# 02_MCU.net
KiCad netlist of a schematic drawn in Altium Designer
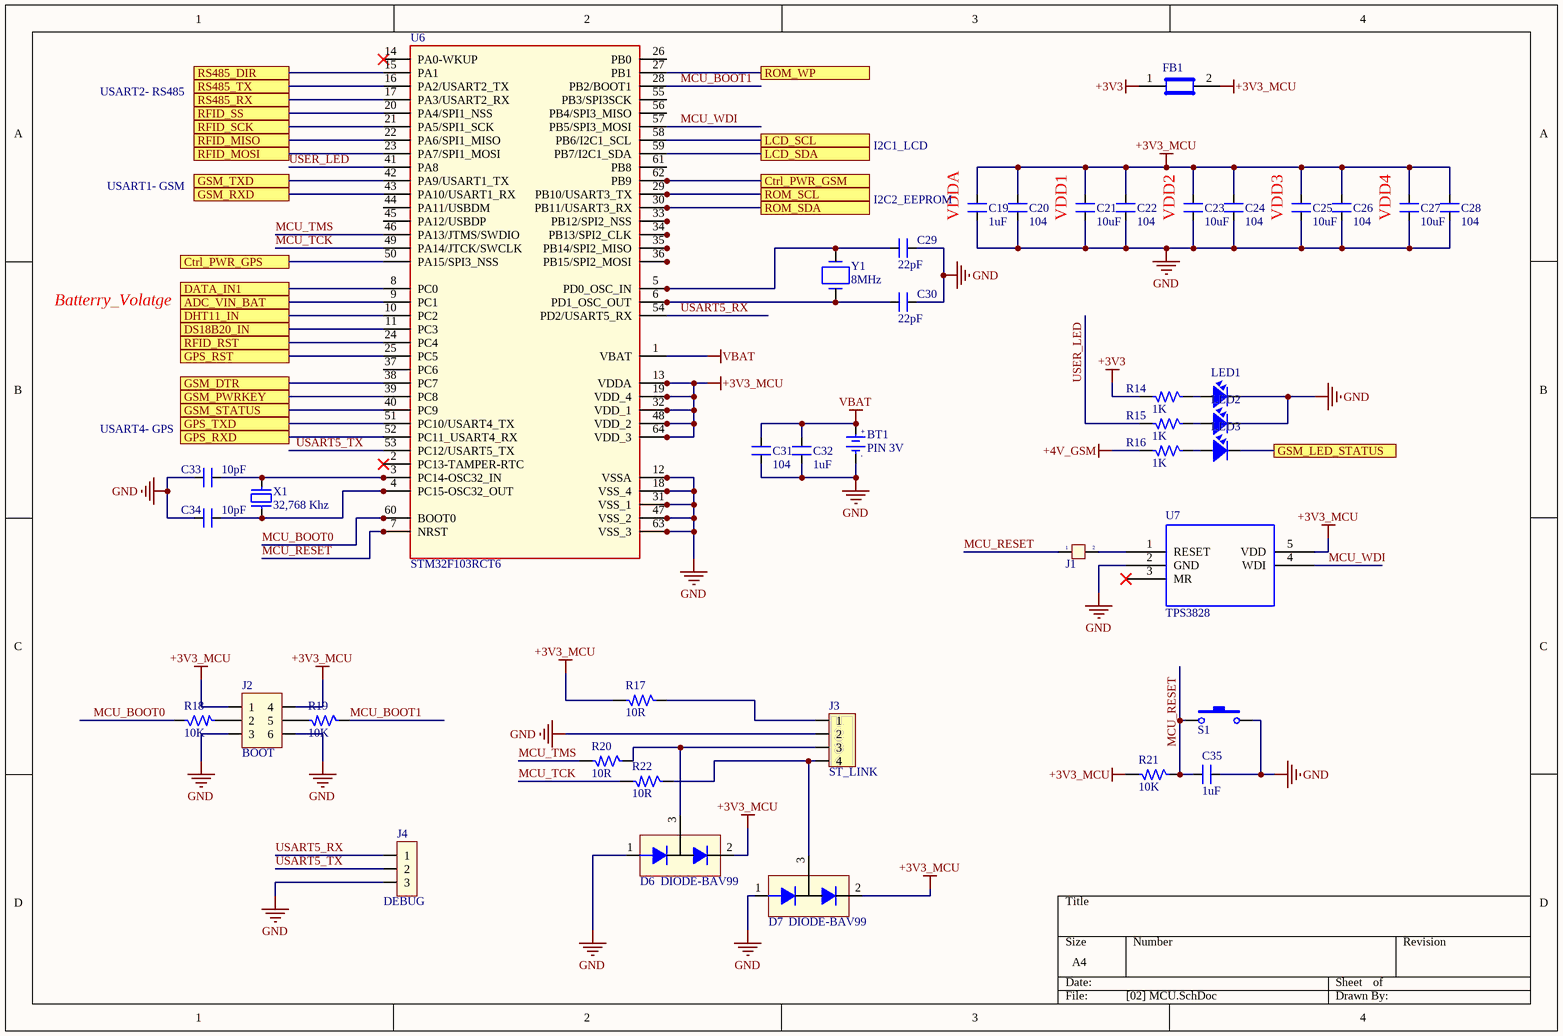
[diagram p0: [02] MCU.SchDoc]

(export (version "E")
  (design (tool "Eeschema 10.0.6"))
  (components
    (comp (ref "BT1")
      (value "PIN 3V")
      (footprint "CR1220 SMD")
      (description "Battery 3VDC")
      (libsource (lib "My Library") (part "PIN 3V"))
    )
    (comp (ref "C19")
      (value "1uF")
      (footprint "C0603 SMT")
      (description "Cap SMD")
      (libsource (lib "GPS_Traking_V1_1") (part "CM"))
    )
    (comp (ref "C20")
      (value "104")
      (footprint "C0603 SMT")
      (description "Cap SMD")
      (libsource (lib "GPS_Traking_V1_1") (part "CM"))
    )
    (comp (ref "C21")
      (value "10uF")
      (footprint "C0603 SMT")
      (description "Cap SMD")
      (libsource (lib "GPS_Traking_V1_1") (part "CM"))
    )
    (comp (ref "C22")
      (value "104")
      (footprint "C0603 SMT")
      (description "Cap SMD")
      (libsource (lib "GPS_Traking_V1_1") (part "CM"))
    )
    (comp (ref "C23")
      (value "10uF")
      (footprint "C0603 SMT")
      (description "Cap SMD")
      (libsource (lib "GPS_Traking_V1_1") (part "CM"))
    )
    (comp (ref "C24")
      (value "104")
      (footprint "C0603 SMT")
      (description "Cap SMD")
      (libsource (lib "GPS_Traking_V1_1") (part "CM"))
    )
    (comp (ref "C25")
      (value "10uF")
      (footprint "C0603 SMT")
      (description "Cap SMD")
      (libsource (lib "GPS_Traking_V1_1") (part "CM"))
    )
    (comp (ref "C26")
      (value "104")
      (footprint "C0603 SMT")
      (description "Cap SMD")
      (libsource (lib "GPS_Traking_V1_1") (part "CM"))
    )
    (comp (ref "C27")
      (value "10uF")
      (footprint "C0603 SMT")
      (description "Cap SMD")
      (libsource (lib "GPS_Traking_V1_1") (part "CM"))
    )
    (comp (ref "C28")
      (value "104")
      (footprint "C0603 SMT")
      (description "Cap SMD")
      (libsource (lib "GPS_Traking_V1_1") (part "CM"))
    )
    (comp (ref "C29")
      (value "22pF")
      (footprint "C0603 SMT")
      (description "Cap SMD")
      (libsource (lib "GPS_Traking_V1_1") (part "CM"))
    )
    (comp (ref "C30")
      (value "22pF")
      (footprint "GPS_Traking_V1_1:C0603 SMT")
      (description "Cap SMD")
      (libsource (lib "My Library") (part "CM"))
    )
    (comp (ref "C31")
      (value "104")
      (footprint "C0603 SMT")
      (description "Cap SMD")
      (libsource (lib "GPS_Traking_V1_1") (part "CM"))
    )
    (comp (ref "C32")
      (value "1uF")
      (footprint "GPS_Traking_V1_1:C0603 SMT")
      (description "Cap SMD")
      (libsource (lib "My Library") (part "CM"))
    )
    (comp (ref "C33")
      (value "10pF")
      (footprint "C0603 SMT")
      (description "Cap SMD")
      (libsource (lib "GPS_Traking_V1_1") (part "CM"))
    )
    (comp (ref "C34")
      (value "10pF")
      (footprint "C0603 SMT")
      (description "Cap SMD")
      (libsource (lib "GPS_Traking_V1_1") (part "CM"))
    )
    (comp (ref "C35")
      (value "1uF")
      (footprint "CAP_0805")
      (description "Cap SMD")
      (libsource (lib "GPS_Traking_V1_1") (part "CM"))
    )
    (comp (ref "D6")
      (value "DIODE-BAV99")
      (footprint "SOT23")
      (description "ZENER, SOT23,")
      (fields
        (field (name "MANUFACTURER") "ON Semiconductor / Fairchild")
        (field (name "MANUFACTURER PART NUMBER") "BAV99")
        (field (name ".CREATOR") "LeKhaLinh")
        (field (name ".CHECKPCB") "LeKhaLinh")
        (field (name ".CHECKSCH") "LeKhaLinh")
      )
      (libsource (lib "GPS_Traking_V1_1") (part "DIODE-BAV99"))
    )
    (comp (ref "D7")
      (value "DIODE-BAV99")
      (footprint "SOT23")
      (description "ZENER, SOT23,")
      (fields
        (field (name "MANUFACTURER") "ON Semiconductor / Fairchild")
        (field (name "MANUFACTURER PART NUMBER") "BAV99")
        (field (name ".CREATOR") "LeKhaLinh")
        (field (name ".CHECKPCB") "LeKhaLinh")
        (field (name ".CHECKSCH") "LeKhaLinh")
      )
      (libsource (lib "GPS_Traking_V1_1") (part "DIODE-BAV99"))
    )
    (comp (ref "FB1")
      (value "BLM21PG600SN1D")
      (footprint "GPS_Traking_V1_1:R0805")
      (description "Ferrite Bead")
      (libsource (lib "khapham") (part "Ferrite Bead"))
    )
    (comp (ref "J1")
      (value "watdog")
      (footprint "JP2")
      (description "Jumper 2")
      (libsource (lib "GPS_Traking_V1_1") (part "JP 2"))
    )
    (comp (ref "J2")
      (value "BOOT")
      (footprint "JP3x2")
      (description "Connector 3x2")
      (libsource (lib "GPS_Traking_V1_1") (part "JP3x2"))
    )
    (comp (ref "J3")
      (value "ST_LINK")
      (footprint "CON_4P")
      (description "Header IDC, 4 x 1 Pin Vertical 2.54mm Pitch (Non-Boxed, Male)")
      (fields
        (field (name "MANUFACTURER") "Würth Elektronik eiSos GmbH")
        (field (name "PARTNO") "613002143121")
        (field (name "CREATED BY") "Karrer Zheng")
      )
      (libsource (lib "My Library") (part "Header4"))
    )
    (comp (ref "J4")
      (value "DEBUG")
      (footprint "JP3")
      (description "Jumper 3")
      (libsource (lib "My Library") (part "JP3"))
    )
    (comp (ref "LED1")
      (value "LED")
      (footprint "LED-0805-Green")
      (description "LED Single colour Green and Red")
      (libsource (lib "My Library") (part "LED"))
    )
    (comp (ref "LED2")
      (value "LED")
      (footprint "LED-0805-Yellow")
      (description "LED Single colour Green and Red")
      (libsource (lib "My Library") (part "LED"))
    )
    (comp (ref "LED3")
      (value "LED")
      (footprint "LED-0805-Red")
      (description "LED Single colour Green and Red")
      (libsource (lib "My Library") (part "LED"))
    )
    (comp (ref "R14")
      (value "1K")
      (footprint "RES-SMD-0805")
      (description "Resistor SMD")
      (libsource (lib "GPS_Traking_V1_1") (part "RM"))
    )
    (comp (ref "R15")
      (value "1K")
      (footprint "RES-SMD-0805")
      (description "Resistor SMD")
      (libsource (lib "GPS_Traking_V1_1") (part "RM"))
    )
    (comp (ref "R16")
      (value "1K")
      (footprint "RES-SMD-0805")
      (description "Resistor SMD")
      (libsource (lib "GPS_Traking_V1_1") (part "RM"))
    )
    (comp (ref "R17")
      (value "10R")
      (footprint "RES-SMD-0805")
      (description "Resistor SMD")
      (libsource (lib "GPS_Traking_V1_1") (part "RM"))
    )
    (comp (ref "R18")
      (value "10K")
      (footprint "R0603 -SMT")
      (description "Resistor SMD")
      (libsource (lib "GPS_Traking_V1_1") (part "RM"))
    )
    (comp (ref "R19")
      (value "10K")
      (footprint "R0603 -SMT")
      (description "Resistor SMD")
      (libsource (lib "GPS_Traking_V1_1") (part "RM"))
    )
    (comp (ref "R20")
      (value "10R")
      (footprint "RES-SMD-0805")
      (description "Resistor SMD")
      (libsource (lib "GPS_Traking_V1_1") (part "RM"))
    )
    (comp (ref "R21")
      (value "10K")
      (footprint "RES-SMD-0805")
      (description "Resistor SMD")
      (libsource (lib "GPS_Traking_V1_1") (part "RM"))
    )
    (comp (ref "R22")
      (value "10R")
      (footprint "RES-SMD-0805")
      (description "Resistor SMD")
      (libsource (lib "GPS_Traking_V1_1") (part "RM"))
    )
    (comp (ref "S1")
      (value "SW-SMD")
      (footprint "SW-SMD")
      (description "Switch")
      (fields (field (name "PUBLISHER") "Altium Limited"))
      (libsource (lib "My Library") (part "SW-SMD"))
    )
    (comp (ref "U6")
      (value "STM32F103RCT6")
      (footprint "LQFP-64")
      (description "MCU 32BIT 256KB FLASH 64LQFP")
      (libsource (lib "GPS_Traking_V1_1") (part "STM32F103RCT6"))
    )
    (comp (ref "U7")
      (value "TPS3828")
      (footprint "TPS3828")
      (libsource (lib "GPS_Traking_V1_1") (part "TPS3828"))
    )
    (comp (ref "X1")
      (value "32,768 Khz")
      (footprint "XT32kn")
      (description "Crystal 32,768kHz for timer real")
      (libsource (lib "GPS_Traking_V1_1") (part "XT32k"))
    )
    (comp (ref "Y1")
      (value "8MHz")
      (footprint "GPS_Traking_V1_1:ABM7_v1_1_BIG")
      (description "CRYSTAL 16MHZ 18PF SMD")
      (fields
        (field (name "MANUFACTURER") "Abracon LLC")
        (field (name "MANUFACTURER PART NUMBER") "ABM7-16.000MHZ-D2Y-T")
        (field (name ".CREATOR") "MM")
        (field (name ".CHECKED PCB") "RF")
        (field (name ".CHECKED SCH") "RF")
      )
      (libsource (lib "GPS_Traking_V1_1") (part "ABM7-16.000MHZ-D2Y-T"))
    )
  )
  (nets
    (net (code "1") (name "+3V3") (class "Default")
      (node (ref "FB1") (pin "1") (pinfunction "1_1") (pintype "passive"))
      (node (ref "R14") (pin "2") (pinfunction "2_2") (pintype "passive"))
    )
    (net (code "2") (name "+3V3_MCU") (class "Default")
      (node (ref "C19") (pin "2") (pinfunction "2_2") (pintype "passive"))
      (node (ref "C20") (pin "2") (pinfunction "2_2") (pintype "passive"))
      (node (ref "C21") (pin "2") (pinfunction "2_2") (pintype "passive"))
      (node (ref "C22") (pin "2") (pinfunction "2_2") (pintype "passive"))
      (node (ref "C23") (pin "2") (pinfunction "2_2") (pintype "passive"))
      (node (ref "C24") (pin "2") (pinfunction "2_2") (pintype "passive"))
      (node (ref "C25") (pin "2") (pinfunction "2_2") (pintype "passive"))
      (node (ref "C26") (pin "2") (pinfunction "2_2") (pintype "passive"))
      (node (ref "C27") (pin "2") (pinfunction "2_2") (pintype "passive"))
      (node (ref "C28") (pin "2") (pinfunction "2_2") (pintype "passive"))
      (node (ref "D6") (pin "2") (pinfunction "2_2") (pintype "passive"))
      (node (ref "D7") (pin "2") (pinfunction "2_2") (pintype "passive"))
      (node (ref "FB1") (pin "2") (pinfunction "2_2") (pintype "passive"))
      (node (ref "J2") (pin "1") (pinfunction "1_1") (pintype "passive"))
      (node (ref "J2") (pin "4") (pinfunction "4_4") (pintype "passive"))
      (node (ref "R17") (pin "2") (pinfunction "2_2") (pintype "passive"))
      (node (ref "R21") (pin "2") (pinfunction "2_2") (pintype "passive"))
      (node (ref "U6") (pin "13") (pinfunction "VDDA_13") (pintype "passive"))
      (node (ref "U6") (pin "19") (pinfunction "VDD_4_19") (pintype "passive"))
      (node (ref "U6") (pin "32") (pinfunction "VDD_1_32") (pintype "passive"))
      (node (ref "U6") (pin "48") (pinfunction "VDD_2_48") (pintype "passive"))
      (node (ref "U6") (pin "64") (pinfunction "VDD_3_64") (pintype "passive"))
      (node (ref "U7") (pin "5") (pinfunction "VDD_5") (pintype "power_in"))
    )
    (net (code "3") (name "+4V_GSM") (class "Default")
      (node (ref "R16") (pin "2") (pinfunction "2_2") (pintype "passive"))
    )
    (net (code "4") (name "/ADC_VIN_BAT") (class "Default")
      (node (ref "U6") (pin "9") (pinfunction "PC1_9") (pintype "passive"))
    )
    (net (code "5") (name "/Ctrl_PWR_GPS") (class "Default")
      (node (ref "U6") (pin "50") (pinfunction "PA15/SPI3_NSS_50") (pintype "passive"))
    )
    (net (code "6") (name "/Ctrl_PWR_GSM") (class "Default")
      (node (ref "U6") (pin "62") (pinfunction "PB9_62") (pintype "passive"))
    )
    (net (code "7") (name "/DATA_IN1") (class "Default")
      (node (ref "U6") (pin "8") (pinfunction "PC0_8") (pintype "passive"))
    )
    (net (code "8") (name "/DHT11_IN") (class "Default")
      (node (ref "U6") (pin "10") (pinfunction "PC2_10") (pintype "passive"))
    )
    (net (code "9") (name "/DS18B20_IN") (class "Default")
      (node (ref "U6") (pin "11") (pinfunction "PC3_11") (pintype "passive"))
    )
    (net (code "10") (name "/GPS_RST") (class "Default")
      (node (ref "U6") (pin "25") (pinfunction "PC5_25") (pintype "passive"))
    )
    (net (code "11") (name "/GPS_RXD") (class "Default")
      (node (ref "U6") (pin "52") (pinfunction "PC11_USART4_RX_52") (pintype "passive"))
    )
    (net (code "12") (name "/GPS_TXD") (class "Default")
      (node (ref "U6") (pin "51") (pinfunction "PC10/USART4_TX_51") (pintype "passive"))
    )
    (net (code "13") (name "/GSM_DTR") (class "Default")
      (node (ref "U6") (pin "38") (pinfunction "PC7_38") (pintype "passive"))
    )
    (net (code "14") (name "/GSM_LED_STATUS") (class "Default")
      (node (ref "LED3") (pin "2") (pinfunction "2_2") (pintype "passive"))
    )
    (net (code "15") (name "/GSM_PWRKEY") (class "Default")
      (node (ref "U6") (pin "39") (pinfunction "PC8_39") (pintype "passive"))
    )
    (net (code "16") (name "/GSM_RXD") (class "Default")
      (node (ref "U6") (pin "43") (pinfunction "PA10/USART1_RX_43") (pintype "passive"))
    )
    (net (code "17") (name "/GSM_STATUS") (class "Default")
      (node (ref "U6") (pin "40") (pinfunction "PC9_40") (pintype "passive"))
    )
    (net (code "18") (name "/GSM_TXD") (class "Default")
      (node (ref "U6") (pin "42") (pinfunction "PA9/USART1_TX_42") (pintype "passive"))
    )
    (net (code "19") (name "/LCD_SCL") (class "Default")
      (node (ref "U6") (pin "58") (pinfunction "PB6/I2C1_SCL_58") (pintype "passive"))
    )
    (net (code "20") (name "/LCD_SDA") (class "Default")
      (node (ref "U6") (pin "59") (pinfunction "PB7/I2C1_SDA_59") (pintype "passive"))
    )
    (net (code "21") (name "/MCU_BOOT0") (class "Default")
      (node (ref "R18") (pin "1") (pinfunction "1_1") (pintype "passive"))
      (node (ref "U6") (pin "60") (pinfunction "BOOT0_60") (pintype "passive"))
    )
    (net (code "22") (name "/MCU_BOOT1") (class "Default")
      (node (ref "R19") (pin "1") (pinfunction "1_1") (pintype "passive"))
      (node (ref "U6") (pin "28") (pinfunction "PB2/BOOT1_28") (pintype "passive"))
    )
    (net (code "23") (name "/MCU_RESET") (class "Default")
      (node (ref "C35") (pin "1") (pinfunction "1_1") (pintype "passive"))
      (node (ref "J1") (pin "1") (pinfunction "1_1") (pintype "passive"))
      (node (ref "R21") (pin "1") (pinfunction "1_1") (pintype "passive"))
      (node (ref "S1") (pin "1") (pinfunction "1_1") (pintype "passive"))
      (node (ref "U6") (pin "7") (pinfunction "NRST_7") (pintype "passive"))
    )
    (net (code "24") (name "/MCU_TCK") (class "Default")
      (node (ref "R22") (pin "2") (pinfunction "2_2") (pintype "passive"))
      (node (ref "U6") (pin "49") (pinfunction "PA14/JTCK/SWCLK_49") (pintype "passive"))
    )
    (net (code "25") (name "/MCU_TMS") (class "Default")
      (node (ref "R20") (pin "2") (pinfunction "2_2") (pintype "passive"))
      (node (ref "U6") (pin "46") (pinfunction "PA13/JTMS/SWDIO_46") (pintype "passive"))
    )
    (net (code "26") (name "/MCU_WDI") (class "Default")
      (node (ref "U6") (pin "57") (pinfunction "PB5/SPI3_MOSI_57") (pintype "passive"))
      (node (ref "U7") (pin "4") (pinfunction "WDI_4") (pintype "passive"))
    )
    (net (code "27") (name "/RFID_MISO") (class "Default")
      (node (ref "U6") (pin "22") (pinfunction "PA6/SPI1_MISO_22") (pintype "passive"))
    )
    (net (code "28") (name "/RFID_MOSI") (class "Default")
      (node (ref "U6") (pin "23") (pinfunction "PA7/SPI1_MOSI_23") (pintype "passive"))
    )
    (net (code "29") (name "/RFID_RST") (class "Default")
      (node (ref "U6") (pin "24") (pinfunction "PC4_24") (pintype "passive"))
    )
    (net (code "30") (name "/RFID_SCK") (class "Default")
      (node (ref "U6") (pin "21") (pinfunction "PA5/SPI1_SCK_21") (pintype "passive"))
    )
    (net (code "31") (name "/RFID_SS") (class "Default")
      (node (ref "U6") (pin "20") (pinfunction "PA4/SPI1_NSS_20") (pintype "passive"))
    )
    (net (code "32") (name "/ROM_SCL") (class "Default")
      (node (ref "U6") (pin "29") (pinfunction "PB10/USART3_TX_29") (pintype "passive"))
    )
    (net (code "33") (name "/ROM_SDA") (class "Default")
      (node (ref "U6") (pin "30") (pinfunction "PB11/USART3_RX_30") (pintype "passive"))
    )
    (net (code "34") (name "/ROM_WP") (class "Default")
      (node (ref "U6") (pin "27") (pinfunction "PB1_27") (pintype "passive"))
    )
    (net (code "35") (name "/RS485_DIR") (class "Default")
      (node (ref "U6") (pin "15") (pinfunction "PA1_15") (pintype "passive"))
    )
    (net (code "36") (name "/RS485_RX") (class "Default")
      (node (ref "U6") (pin "17") (pinfunction "PA3/USART2_RX_17") (pintype "passive"))
    )
    (net (code "37") (name "/RS485_TX") (class "Default")
      (node (ref "U6") (pin "16") (pinfunction "PA2/USART2_TX_16") (pintype "passive"))
    )
    (net (code "38") (name "/USART5_RX") (class "Default")
      (node (ref "J4") (pin "1") (pinfunction "1_1") (pintype "passive"))
      (node (ref "U6") (pin "54") (pinfunction "PD2/USART5_RX_54") (pintype "passive"))
    )
    (net (code "39") (name "/USART5_TX") (class "Default")
      (node (ref "J4") (pin "2") (pinfunction "2_2") (pintype "passive"))
      (node (ref "U6") (pin "53") (pinfunction "PC12/USART5_TX_53") (pintype "passive"))
    )
    (net (code "40") (name "/USER_LED") (class "Default")
      (node (ref "R15") (pin "2") (pinfunction "2_2") (pintype "passive"))
      (node (ref "U6") (pin "41") (pinfunction "PA8_41") (pintype "passive"))
    )
    (net (code "41") (name "GND") (class "Default")
      (node (ref "BT1") (pin "2") (pinfunction "GND_2") (pintype "passive"))
      (node (ref "C19") (pin "1") (pinfunction "1_1") (pintype "passive"))
      (node (ref "C20") (pin "1") (pinfunction "1_1") (pintype "passive"))
      (node (ref "C21") (pin "1") (pinfunction "1_1") (pintype "passive"))
      (node (ref "C22") (pin "1") (pinfunction "1_1") (pintype "passive"))
      (node (ref "C23") (pin "1") (pinfunction "1_1") (pintype "passive"))
      (node (ref "C24") (pin "1") (pinfunction "1_1") (pintype "passive"))
      (node (ref "C25") (pin "1") (pinfunction "1_1") (pintype "passive"))
      (node (ref "C26") (pin "1") (pinfunction "1_1") (pintype "passive"))
      (node (ref "C27") (pin "1") (pinfunction "1_1") (pintype "passive"))
      (node (ref "C28") (pin "1") (pinfunction "1_1") (pintype "passive"))
      (node (ref "C29") (pin "2") (pinfunction "2_2") (pintype "passive"))
      (node (ref "C30") (pin "2") (pinfunction "2_2") (pintype "passive"))
      (node (ref "C31") (pin "1") (pinfunction "1_1") (pintype "passive"))
      (node (ref "C32") (pin "1") (pinfunction "1_1") (pintype "passive"))
      (node (ref "C33") (pin "2") (pinfunction "2_2") (pintype "passive"))
      (node (ref "C34") (pin "2") (pinfunction "2_2") (pintype "passive"))
      (node (ref "C35") (pin "2") (pinfunction "2_2") (pintype "passive"))
      (node (ref "D6") (pin "1") (pinfunction "1_1") (pintype "passive"))
      (node (ref "D7") (pin "1") (pinfunction "1_1") (pintype "passive"))
      (node (ref "J2") (pin "3") (pinfunction "3_3") (pintype "passive"))
      (node (ref "J2") (pin "6") (pinfunction "6_6") (pintype "passive"))
      (node (ref "J3") (pin "2") (pinfunction "2_2") (pintype "passive"))
      (node (ref "J4") (pin "3") (pinfunction "3_3") (pintype "passive"))
      (node (ref "LED1") (pin "2") (pinfunction "2_2") (pintype "passive"))
      (node (ref "LED2") (pin "2") (pinfunction "2_2") (pintype "passive"))
      (node (ref "S1") (pin "2") (pinfunction "2_2") (pintype "passive"))
      (node (ref "U6") (pin "12") (pinfunction "VSSA_12") (pintype "passive"))
      (node (ref "U6") (pin "18") (pinfunction "VSS_4_18") (pintype "passive"))
      (node (ref "U6") (pin "31") (pinfunction "VSS_1_31") (pintype "passive"))
      (node (ref "U6") (pin "47") (pinfunction "VSS_2_47") (pintype "passive"))
      (node (ref "U6") (pin "63") (pinfunction "VSS_3_63") (pintype "passive"))
      (node (ref "U7") (pin "2") (pinfunction "GND_2") (pintype "power_in"))
    )
    (net (code "42") (name "Net-(D6-Pad3)") (class "Default")
      (node (ref "D6") (pin "3") (pinfunction "3_3") (pintype "passive"))
      (node (ref "J3") (pin "3") (pinfunction "3_3") (pintype "passive"))
      (node (ref "R20") (pin "1") (pinfunction "1_1") (pintype "passive"))
    )
    (net (code "43") (name "Net-(D7-Pad3)") (class "Default")
      (node (ref "D7") (pin "3") (pinfunction "3_3") (pintype "passive"))
      (node (ref "J3") (pin "4") (pinfunction "4_4") (pintype "passive"))
      (node (ref "R22") (pin "1") (pinfunction "1_1") (pintype "passive"))
    )
    (net (code "44") (name "Net-(J2-Pad2)") (class "Default")
      (node (ref "J2") (pin "2") (pinfunction "2_2") (pintype "passive"))
      (node (ref "R18") (pin "2") (pinfunction "2_2") (pintype "passive"))
    )
    (net (code "45") (name "Net-(J2-Pad5)") (class "Default")
      (node (ref "J2") (pin "5") (pinfunction "5_5") (pintype "passive"))
      (node (ref "R19") (pin "2") (pinfunction "2_2") (pintype "passive"))
    )
    (net (code "46") (name "Net-(J3-Pad1)") (class "Default")
      (node (ref "J3") (pin "1") (pinfunction "1_1") (pintype "passive"))
      (node (ref "R17") (pin "1") (pinfunction "1_1") (pintype "passive"))
    )
    (net (code "47") (name "Net-(LED1-Pad1)") (class "Default")
      (node (ref "LED1") (pin "1") (pinfunction "1_1") (pintype "passive"))
      (node (ref "R14") (pin "1") (pinfunction "1_1") (pintype "passive"))
    )
    (net (code "48") (name "Net-(LED2-Pad1)") (class "Default")
      (node (ref "LED2") (pin "1") (pinfunction "1_1") (pintype "passive"))
      (node (ref "R15") (pin "1") (pinfunction "1_1") (pintype "passive"))
    )
    (net (code "49") (name "Net-(LED3-Pad1)") (class "Default")
      (node (ref "LED3") (pin "1") (pinfunction "1_1") (pintype "passive"))
      (node (ref "R16") (pin "1") (pinfunction "1_1") (pintype "passive"))
    )
    (net (code "50") (name "Net-(U6-PC14-OSC32_IN)") (class "Default")
      (node (ref "C33") (pin "1") (pinfunction "1_1") (pintype "passive"))
      (node (ref "U6") (pin "3") (pinfunction "PC14-OSC32_IN_3") (pintype "passive"))
      (node (ref "X1") (pin "1") (pinfunction "1_1") (pintype "passive"))
    )
    (net (code "51") (name "Net-(U6-PC15-OSC32_OUT)") (class "Default")
      (node (ref "C34") (pin "1") (pinfunction "1_1") (pintype "passive"))
      (node (ref "U6") (pin "4") (pinfunction "PC15-OSC32_OUT_4") (pintype "passive"))
      (node (ref "X1") (pin "2") (pinfunction "2_2") (pintype "passive"))
    )
    (net (code "52") (name "Net-(U6-PD0_OSC_IN)") (class "Default")
      (node (ref "C29") (pin "1") (pinfunction "1_1") (pintype "passive"))
      (node (ref "U6") (pin "5") (pinfunction "PD0_OSC_IN_5") (pintype "passive"))
      (node (ref "Y1") (pin "2") (pinfunction "2_2") (pintype "passive"))
    )
    (net (code "53") (name "Net-(U6-PD1_OSC_OUT)") (class "Default")
      (node (ref "C30") (pin "1") (pinfunction "1_1") (pintype "passive"))
      (node (ref "U6") (pin "6") (pinfunction "PD1_OSC_OUT_6") (pintype "passive"))
      (node (ref "Y1") (pin "1") (pinfunction "1_1") (pintype "passive"))
    )
    (net (code "54") (name "Net-(U7-RESET)") (class "Default")
      (node (ref "J1") (pin "2") (pinfunction "2_2") (pintype "passive"))
      (node (ref "U7") (pin "1") (pinfunction "RESET_1") (pintype "passive"))
    )
    (net (code "55") (name "VBAT") (class "Default")
      (node (ref "BT1") (pin "1") (pinfunction "+3V_1") (pintype "passive"))
      (node (ref "C31") (pin "2") (pinfunction "2_2") (pintype "passive"))
      (node (ref "C32") (pin "2") (pinfunction "2_2") (pintype "passive"))
      (node (ref "U6") (pin "1") (pinfunction "VBAT_1") (pintype "passive"))
    )
    (net (code "56") (name "unconnected-(U6-PA0-WKUP-Pad14)") (class "Default")
      (node (ref "U6") (pin "14") (pinfunction "PA0-WKUP_14") (pintype "passive+no_connect"))
    )
    (net (code "57") (name "unconnected-(U6-PA11{slash}USBDM-Pad44)") (class "Default")
      (node (ref "U6") (pin "44") (pinfunction "PA11/USBDM_44") (pintype "passive"))
    )
    (net (code "58") (name "unconnected-(U6-PA12{slash}USBDP-Pad45)") (class "Default")
      (node (ref "U6") (pin "45") (pinfunction "PA12/USBDP_45") (pintype "passive"))
    )
    (net (code "59") (name "unconnected-(U6-PB0-Pad26)") (class "Default")
      (node (ref "U6") (pin "26") (pinfunction "PB0_26") (pintype "passive"))
    )
    (net (code "60") (name "unconnected-(U6-PB3{slash}SPI3SCK-Pad55)") (class "Default")
      (node (ref "U6") (pin "55") (pinfunction "PB3/SPI3SCK_55") (pintype "passive"))
    )
    (net (code "61") (name "unconnected-(U6-PB4{slash}SPI3_MISO-Pad56)") (class "Default")
      (node (ref "U6") (pin "56") (pinfunction "PB4/SPI3_MISO_56") (pintype "passive"))
    )
    (net (code "62") (name "unconnected-(U6-PB8-Pad61)") (class "Default")
      (node (ref "U6") (pin "61") (pinfunction "PB8_61") (pintype "passive"))
    )
    (net (code "63") (name "unconnected-(U6-PB12{slash}SPI2_NSS-Pad33)") (class "Default")
      (node (ref "U6") (pin "33") (pinfunction "PB12/SPI2_NSS_33") (pintype "passive"))
    )
    (net (code "64") (name "unconnected-(U6-PB13{slash}SPI2_CLK-Pad34)") (class "Default")
      (node (ref "U6") (pin "34") (pinfunction "PB13/SPI2_CLK_34") (pintype "passive"))
    )
    (net (code "65") (name "unconnected-(U6-PB14{slash}SPI2_MISO-Pad35)") (class "Default")
      (node (ref "U6") (pin "35") (pinfunction "PB14/SPI2_MISO_35") (pintype "passive"))
    )
    (net (code "66") (name "unconnected-(U6-PB15{slash}SPI2_MOSI-Pad36)") (class "Default")
      (node (ref "U6") (pin "36") (pinfunction "PB15/SPI2_MOSI_36") (pintype "passive"))
    )
    (net (code "67") (name "unconnected-(U6-PC6-Pad37)") (class "Default")
      (node (ref "U6") (pin "37") (pinfunction "PC6_37") (pintype "passive"))
    )
    (net (code "68") (name "unconnected-(U6-PC13-TAMPER-RTC-Pad2)") (class "Default")
      (node (ref "U6") (pin "2") (pinfunction "PC13-TAMPER-RTC_2") (pintype "passive+no_connect"))
    )
    (net (code "69") (name "unconnected-(U7-MR-Pad3)") (class "Default")
      (node (ref "U7") (pin "3") (pinfunction "MR_3") (pintype "passive+no_connect"))
    )
  )
)
